# A-FINAL_SCHEMATIC.net
KiCad netlist of a schematic drawn in EAGLE
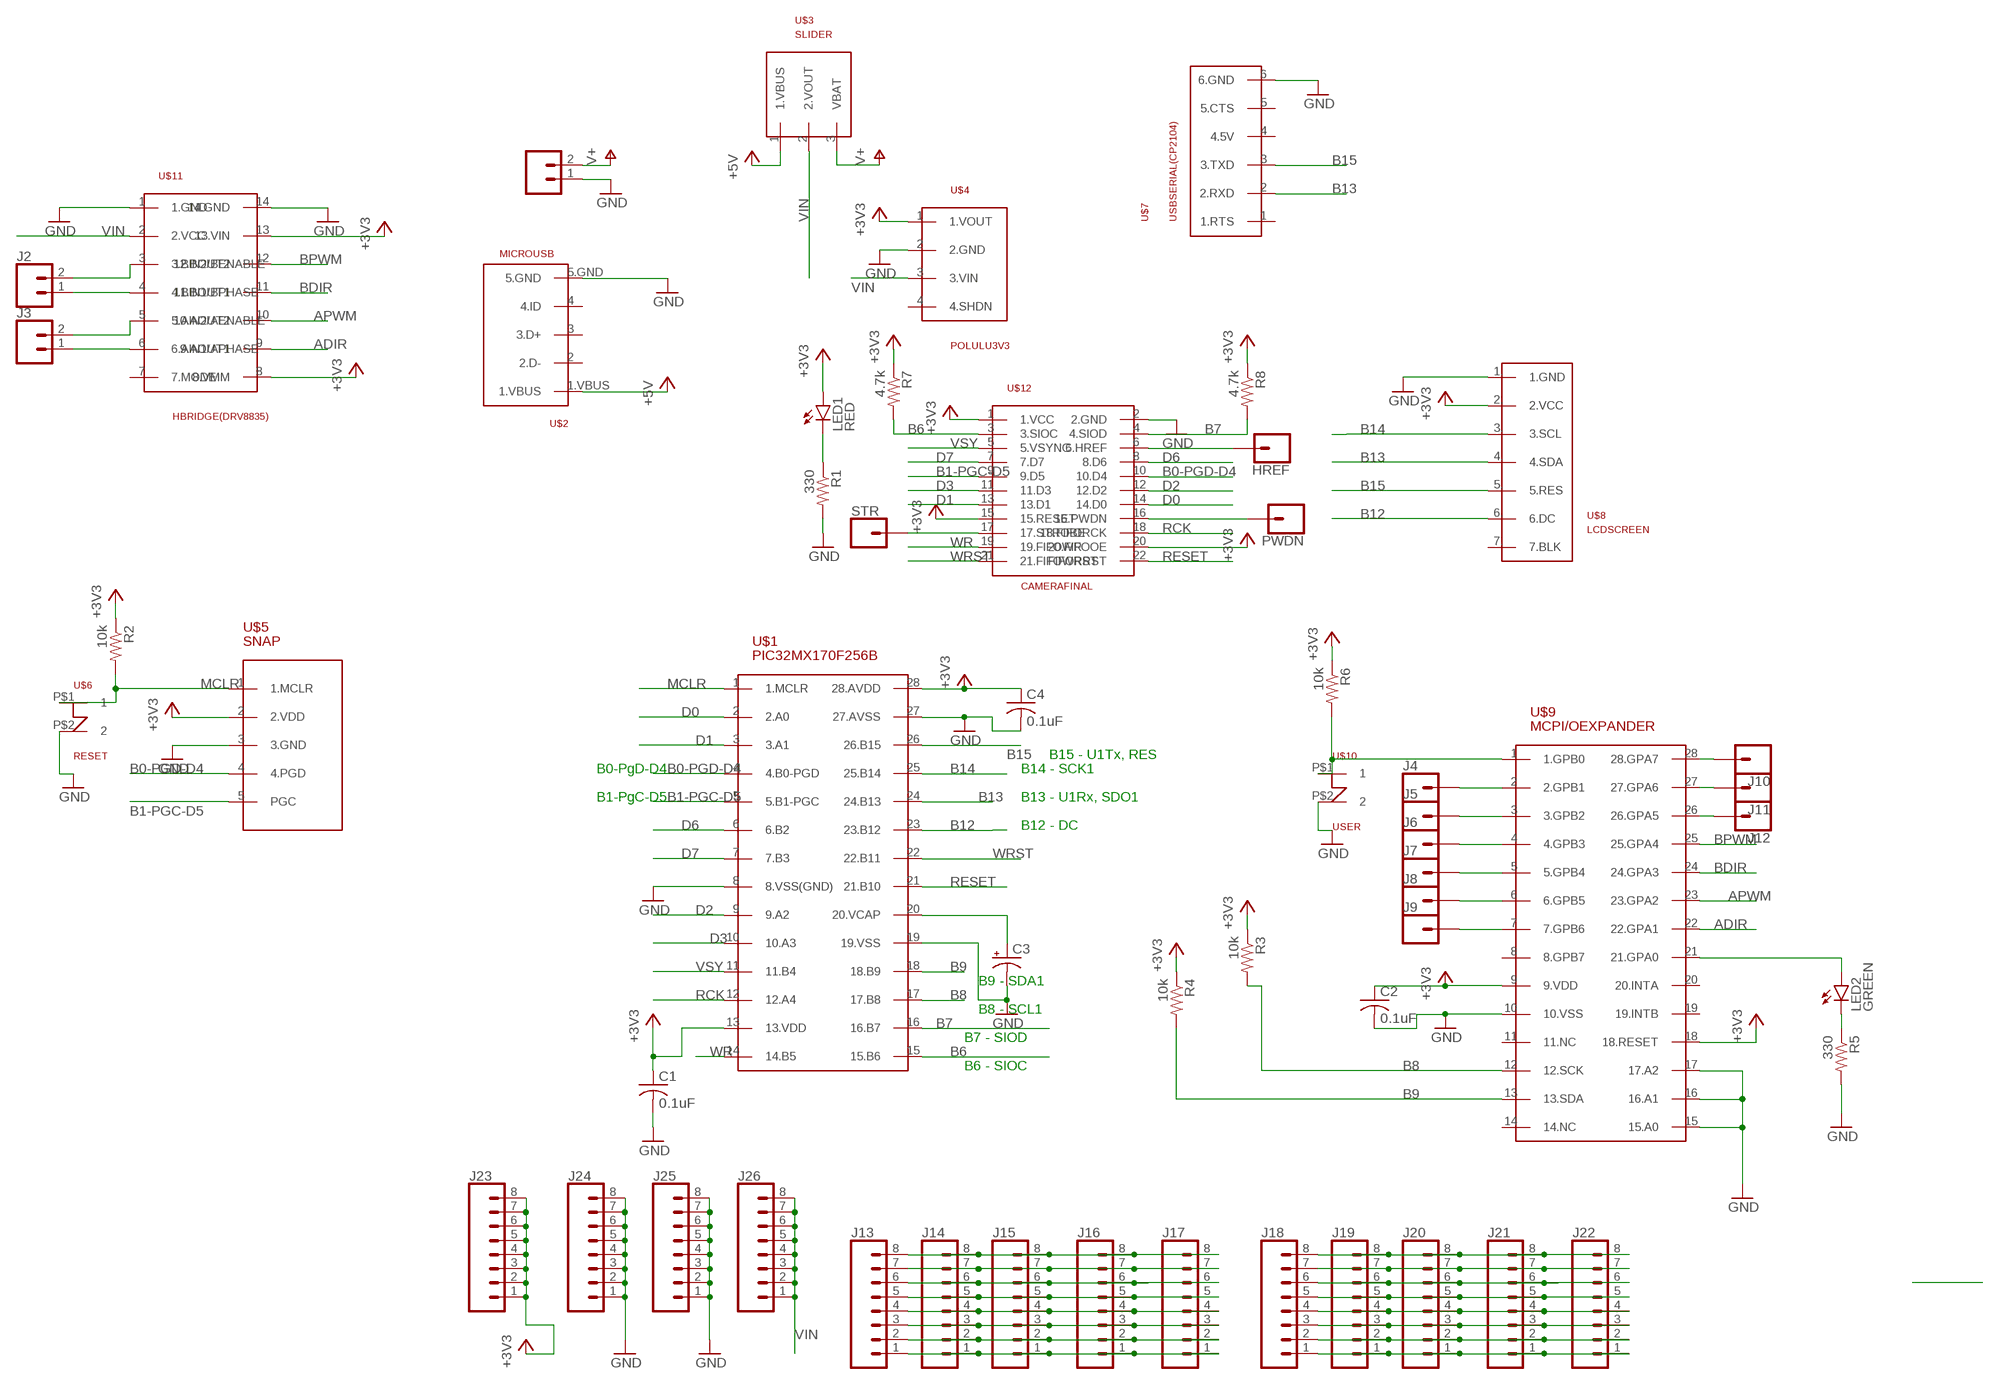
[diagram p0: schematic, sheet 1]

(export (version "E")
  (design (tool "Eeschema 10.0.6"))
  (components
    (comp (ref "C1")
      (value "0.1uF")
      (footprint "eagle-import:C025-030X050")
      (libsource (lib "eagle-import") (part "C-US025-030X050"))
    )
    (comp (ref "C2")
      (value "0.1uF")
      (footprint "eagle-import:C025-030X050")
      (libsource (lib "eagle-import") (part "C-US025-030X050"))
    )
    (comp (ref "C3")
      (value "CPOL-USB45181B")
      (footprint "eagle-import:B45181B")
      (libsource (lib "eagle-import") (part "CPOL-USB45181B"))
    )
    (comp (ref "C4")
      (value "0.1uF")
      (footprint "eagle-import:C025-030X050")
      (libsource (lib "eagle-import") (part "C-US025-030X050"))
    )
    (comp (ref "HREF")
      (value "CONN_01")
      (footprint "eagle-import:1X01")
      (libsource (lib "eagle-import") (part "CONN_01"))
    )
    (comp (ref "J1")
      (value "CONN_02-JST-2-PTH-NO_SILK")
      (footprint "eagle-import:JST-2-PTH-NS")
      (libsource (lib "eagle-import") (part "CONN_02-JST-2-PTH-NO_SILK"))
    )
    (comp (ref "J2")
      (value "CONN_02")
      (footprint "eagle-import:1X02")
      (libsource (lib "eagle-import") (part "CONN_02"))
    )
    (comp (ref "J3")
      (value "CONN_02")
      (footprint "eagle-import:1X02")
      (libsource (lib "eagle-import") (part "CONN_02"))
    )
    (comp (ref "J4")
      (value "CONN_01")
      (footprint "eagle-import:1X01")
      (libsource (lib "eagle-import") (part "CONN_01"))
    )
    (comp (ref "J5")
      (value "CONN_01")
      (footprint "eagle-import:1X01")
      (libsource (lib "eagle-import") (part "CONN_01"))
    )
    (comp (ref "J6")
      (value "CONN_01")
      (footprint "eagle-import:1X01")
      (libsource (lib "eagle-import") (part "CONN_01"))
    )
    (comp (ref "J7")
      (value "CONN_01")
      (footprint "eagle-import:1X01")
      (libsource (lib "eagle-import") (part "CONN_01"))
    )
    (comp (ref "J8")
      (value "CONN_01")
      (footprint "eagle-import:1X01")
      (libsource (lib "eagle-import") (part "CONN_01"))
    )
    (comp (ref "J9")
      (value "CONN_01")
      (footprint "eagle-import:1X01")
      (libsource (lib "eagle-import") (part "CONN_01"))
    )
    (comp (ref "J10")
      (value "CONN_01")
      (footprint "eagle-import:1X01")
      (libsource (lib "eagle-import") (part "CONN_01"))
    )
    (comp (ref "J11")
      (value "CONN_01")
      (footprint "eagle-import:1X01")
      (libsource (lib "eagle-import") (part "CONN_01"))
    )
    (comp (ref "J12")
      (value "CONN_01")
      (footprint "eagle-import:1X01")
      (libsource (lib "eagle-import") (part "CONN_01"))
    )
    (comp (ref "J13")
      (value "CONN_08\"")
      (footprint "eagle-import:1X08")
      (libsource (lib "eagle-import") (part "CONN_08{dblquote}"))
    )
    (comp (ref "J14")
      (value "CONN_08\"")
      (footprint "eagle-import:1X08")
      (libsource (lib "eagle-import") (part "CONN_08{dblquote}"))
    )
    (comp (ref "J15")
      (value "CONN_08\"")
      (footprint "eagle-import:1X08")
      (libsource (lib "eagle-import") (part "CONN_08{dblquote}"))
    )
    (comp (ref "J16")
      (value "CONN_08\"")
      (footprint "eagle-import:1X08")
      (libsource (lib "eagle-import") (part "CONN_08{dblquote}"))
    )
    (comp (ref "J17")
      (value "CONN_08\"")
      (footprint "eagle-import:1X08")
      (libsource (lib "eagle-import") (part "CONN_08{dblquote}"))
    )
    (comp (ref "J18")
      (value "CONN_08\"")
      (footprint "eagle-import:1X08")
      (libsource (lib "eagle-import") (part "CONN_08{dblquote}"))
    )
    (comp (ref "J19")
      (value "CONN_08\"")
      (footprint "eagle-import:1X08")
      (libsource (lib "eagle-import") (part "CONN_08{dblquote}"))
    )
    (comp (ref "J20")
      (value "CONN_08\"")
      (footprint "eagle-import:1X08")
      (libsource (lib "eagle-import") (part "CONN_08{dblquote}"))
    )
    (comp (ref "J21")
      (value "CONN_08\"")
      (footprint "eagle-import:1X08")
      (libsource (lib "eagle-import") (part "CONN_08{dblquote}"))
    )
    (comp (ref "J22")
      (value "CONN_08\"")
      (footprint "eagle-import:1X08")
      (libsource (lib "eagle-import") (part "CONN_08{dblquote}"))
    )
    (comp (ref "J23")
      (value "CONN_08\"")
      (footprint "eagle-import:1X08")
      (libsource (lib "eagle-import") (part "CONN_08{dblquote}"))
    )
    (comp (ref "J24")
      (value "CONN_08\"")
      (footprint "eagle-import:1X08")
      (libsource (lib "eagle-import") (part "CONN_08{dblquote}"))
    )
    (comp (ref "J25")
      (value "CONN_08\"")
      (footprint "eagle-import:1X08")
      (libsource (lib "eagle-import") (part "CONN_08{dblquote}"))
    )
    (comp (ref "J26")
      (value "CONN_08\"")
      (footprint "eagle-import:1X08")
      (libsource (lib "eagle-import") (part "CONN_08{dblquote}"))
    )
    (comp (ref "LED1")
      (value "RED")
      (footprint "eagle-import:LED3MM")
      (libsource (lib "eagle-import") (part "LED3MM"))
    )
    (comp (ref "LED2")
      (value "GREEN")
      (footprint "eagle-import:LED3MM")
      (libsource (lib "eagle-import") (part "LED3MM"))
    )
    (comp (ref "PWDN")
      (value "CONN_01")
      (footprint "eagle-import:1X01")
      (libsource (lib "eagle-import") (part "CONN_01"))
    )
    (comp (ref "R1")
      (value "330")
      (footprint "eagle-import:0207_10")
      (libsource (lib "eagle-import") (part "R-US_0207/10"))
    )
    (comp (ref "R2")
      (value "10k")
      (footprint "eagle-import:0207_10")
      (libsource (lib "eagle-import") (part "R-US_0207/10"))
    )
    (comp (ref "R3")
      (value "10k")
      (footprint "eagle-import:0207_10")
      (libsource (lib "eagle-import") (part "R-US_0207/10"))
    )
    (comp (ref "R4")
      (value "10k")
      (footprint "eagle-import:0207_10")
      (libsource (lib "eagle-import") (part "R-US_0207/10"))
    )
    (comp (ref "R5")
      (value "330")
      (footprint "eagle-import:0207_10")
      (libsource (lib "eagle-import") (part "R-US_0207/10"))
    )
    (comp (ref "R6")
      (value "10k")
      (footprint "eagle-import:0207_10")
      (libsource (lib "eagle-import") (part "R-US_0207/10"))
    )
    (comp (ref "R7")
      (value "4.7k")
      (footprint "eagle-import:0207_10")
      (libsource (lib "eagle-import") (part "R-US_0207/10"))
    )
    (comp (ref "R8")
      (value "4.7k")
      (footprint "eagle-import:0207_10")
      (libsource (lib "eagle-import") (part "R-US_0207/10"))
    )
    (comp (ref "STR")
      (value "CONN_01")
      (footprint "eagle-import:1X01")
      (libsource (lib "eagle-import") (part "CONN_01"))
    )
    (comp (ref "U$1")
      (value "PIC32MX170F256B")
      (footprint "eagle-import:DIL28-3")
      (libsource (lib "eagle-import") (part "PIC32MX170F256B"))
    )
    (comp (ref "U$2")
      (value "MICROUSB")
      (footprint "eagle-import:MICROUSB")
      (libsource (lib "eagle-import") (part "MICROUSB"))
    )
    (comp (ref "U$3")
      (value "SLIDER")
      (footprint "eagle-import:SLIDE")
      (libsource (lib "eagle-import") (part "SLIDER"))
    )
    (comp (ref "U$4")
      (value "POLULU3V3")
      (footprint "eagle-import:POLULU3V3")
      (libsource (lib "eagle-import") (part "POLULU3V3"))
    )
    (comp (ref "U$5")
      (value "SNAP")
      (footprint "eagle-import:1X05")
      (libsource (lib "eagle-import") (part "SNAP"))
    )
    (comp (ref "U$6")
      (value "RESET")
      (footprint "eagle-import:PUSH")
      (libsource (lib "eagle-import") (part "PUSH"))
    )
    (comp (ref "U$7")
      (value "USBSERIAL(CP2104)")
      (footprint "eagle-import:USBSERIAL(CP2104)")
      (libsource (lib "eagle-import") (part "USBSERIAL(CP2104)"))
    )
    (comp (ref "U$8")
      (value "LCDSCREEN")
      (footprint "eagle-import:LCDSCREEN")
      (libsource (lib "eagle-import") (part "LCDSCREEN"))
    )
    (comp (ref "U$9")
      (value "MCPI/OEXPANDER")
      (footprint "eagle-import:MCPI_OEXPANDER")
      (libsource (lib "eagle-import") (part "MCPI/OEXPANDER"))
    )
    (comp (ref "U$10")
      (value "USER")
      (footprint "eagle-import:PUSH")
      (libsource (lib "eagle-import") (part "PUSH"))
    )
    (comp (ref "U$11")
      (value "HBRIDGE(DRV8835)")
      (footprint "eagle-import:HBRIDGE(DRV8835)")
      (libsource (lib "eagle-import") (part "HBRIDGE(DRV8835)"))
    )
    (comp (ref "U$12")
      (value "CAMERAFINAL")
      (footprint "eagle-import:CAMERA_FINAL")
      (libsource (lib "eagle-import") (part "CAMERAFINAL"))
    )
  )
  (nets
    (net (code "1") (name "+3V3") (class "Default")
      (node (ref "C1") (pin "1") (pinfunction "1_1") (pintype "passive"))
      (node (ref "C2") (pin "1") (pinfunction "1_1") (pintype "passive"))
      (node (ref "C4") (pin "1") (pinfunction "1_1") (pintype "passive"))
      (node (ref "J23") (pin "1") (pinfunction "1_1") (pintype "passive"))
      (node (ref "J23") (pin "2") (pinfunction "2_2") (pintype "passive"))
      (node (ref "J23") (pin "3") (pinfunction "3_3") (pintype "passive"))
      (node (ref "J23") (pin "4") (pinfunction "4_4") (pintype "passive"))
      (node (ref "J23") (pin "5") (pinfunction "5_5") (pintype "passive"))
      (node (ref "J23") (pin "6") (pinfunction "6_6") (pintype "passive"))
      (node (ref "J23") (pin "7") (pinfunction "7_7") (pintype "passive"))
      (node (ref "J23") (pin "8") (pinfunction "8_8") (pintype "passive"))
      (node (ref "LED1") (pin "A") (pinfunction "A_A") (pintype "passive"))
      (node (ref "R2") (pin "1") (pinfunction "1_1") (pintype "passive"))
      (node (ref "R3") (pin "1") (pinfunction "1_1") (pintype "passive"))
      (node (ref "R4") (pin "1") (pinfunction "1_1") (pintype "passive"))
      (node (ref "R6") (pin "1") (pinfunction "1_1") (pintype "passive"))
      (node (ref "R7") (pin "1") (pinfunction "1_1") (pintype "passive"))
      (node (ref "R8") (pin "1") (pinfunction "1_1") (pintype "passive"))
      (node (ref "U$1") (pin "13") (pinfunction "13.VDD_13") (pintype "bidirectional"))
      (node (ref "U$1") (pin "28") (pinfunction "28.AVDD_28") (pintype "bidirectional"))
      (node (ref "U$11") (pin "13") (pinfunction "13.VIN_13") (pintype "bidirectional"))
      (node (ref "U$11") (pin "8") (pinfunction "8.VMM_8") (pintype "bidirectional"))
      (node (ref "U$12") (pin "1") (pinfunction "1.VCC_1") (pintype "bidirectional"))
      (node (ref "U$12") (pin "15") (pinfunction "15.RESET_15") (pintype "bidirectional"))
      (node (ref "U$12") (pin "20") (pinfunction "20.FIFOOE_20") (pintype "bidirectional"))
      (node (ref "U$4") (pin "1") (pinfunction "1.VOUT_1") (pintype "bidirectional"))
      (node (ref "U$5") (pin "2") (pinfunction "2.VDD_2") (pintype "bidirectional"))
      (node (ref "U$8") (pin "2.") (pinfunction "2.VCC_2.") (pintype "bidirectional"))
      (node (ref "U$9") (pin "18") (pinfunction "18.RESET_18") (pintype "bidirectional"))
      (node (ref "U$9") (pin "9") (pinfunction "9.VDD_9") (pintype "bidirectional"))
    )
    (net (code "2") (name "+5V") (class "Default")
      (node (ref "U$2") (pin "1.VBUS") (pinfunction "1.VBUS_1.VBUS") (pintype "bidirectional"))
      (node (ref "U$3") (pin "1") (pinfunction "1.VBUS_1") (pintype "bidirectional"))
    )
    (net (code "3") (name "/ADIR") (class "Default")
      (node (ref "U$11") (pin "9") (pinfunction "9.AOUT1_9") (pintype "bidirectional"))
      (node (ref "U$9") (pin "22") (pinfunction "22.GPA1_22") (pintype "bidirectional"))
    )
    (net (code "4") (name "/APWM") (class "Default")
      (node (ref "U$11") (pin "10") (pinfunction "10.AOUT2_10") (pintype "bidirectional"))
      (node (ref "U$9") (pin "23") (pinfunction "23.GPA2_23") (pintype "bidirectional"))
    )
    (net (code "5") (name "/B0-PGD-D4") (class "Default")
      (node (ref "U$1") (pin "4") (pinfunction "4.B0-PGD_4") (pintype "bidirectional"))
      (node (ref "U$12") (pin "10") (pinfunction "10.D4_10") (pintype "bidirectional"))
      (node (ref "U$5") (pin "4") (pinfunction "4.PGD_4") (pintype "bidirectional"))
    )
    (net (code "6") (name "/B1-PGC-D5") (class "Default")
      (node (ref "U$1") (pin "5") (pinfunction "5.B1-PGC_5") (pintype "bidirectional"))
      (node (ref "U$12") (pin "9") (pinfunction "9.D5_9") (pintype "bidirectional"))
      (node (ref "U$5") (pin "5") (pinfunction "PGC_5") (pintype "bidirectional"))
    )
    (net (code "7") (name "/B6") (class "Default")
      (node (ref "R7") (pin "2") (pinfunction "2_2") (pintype "passive"))
      (node (ref "U$1") (pin "15") (pinfunction "15.B6_15") (pintype "bidirectional"))
      (node (ref "U$12") (pin "3") (pinfunction "3.SIOC_3") (pintype "bidirectional"))
    )
    (net (code "8") (name "/B7") (class "Default")
      (node (ref "R8") (pin "2") (pinfunction "2_2") (pintype "passive"))
      (node (ref "U$1") (pin "16") (pinfunction "16.B7_16") (pintype "bidirectional"))
      (node (ref "U$12") (pin "4") (pinfunction "4.SIOD_4") (pintype "bidirectional"))
    )
    (net (code "9") (name "/B8") (class "Default")
      (node (ref "R3") (pin "2") (pinfunction "2_2") (pintype "passive"))
      (node (ref "U$1") (pin "17") (pinfunction "17.B8_17") (pintype "bidirectional"))
      (node (ref "U$9") (pin "12") (pinfunction "12.SCK_12") (pintype "bidirectional"))
    )
    (net (code "10") (name "/B9") (class "Default")
      (node (ref "R4") (pin "2") (pinfunction "2_2") (pintype "passive"))
      (node (ref "U$1") (pin "18") (pinfunction "18.B9_18") (pintype "bidirectional"))
      (node (ref "U$9") (pin "13") (pinfunction "13.SDA_13") (pintype "bidirectional"))
    )
    (net (code "11") (name "/B12") (class "Default")
      (node (ref "U$1") (pin "23") (pinfunction "23.B12_23") (pintype "bidirectional"))
      (node (ref "U$8") (pin "6.") (pinfunction "6.DC_6.") (pintype "bidirectional"))
    )
    (net (code "12") (name "/B13") (class "Default")
      (node (ref "U$1") (pin "24") (pinfunction "24.B13_24") (pintype "bidirectional"))
      (node (ref "U$7") (pin "2") (pinfunction "2.RXD_2") (pintype "bidirectional"))
      (node (ref "U$8") (pin "4.") (pinfunction "4.SDA_4.") (pintype "bidirectional"))
    )
    (net (code "13") (name "/B14") (class "Default")
      (node (ref "U$1") (pin "25") (pinfunction "25.B14_25") (pintype "bidirectional"))
      (node (ref "U$8") (pin "3.") (pinfunction "3.SCL_3.") (pintype "bidirectional"))
    )
    (net (code "14") (name "/B15") (class "Default")
      (node (ref "U$1") (pin "26") (pinfunction "26.B15_26") (pintype "bidirectional"))
      (node (ref "U$7") (pin "3") (pinfunction "3.TXD_3") (pintype "bidirectional"))
      (node (ref "U$8") (pin "5.") (pinfunction "5.RES_5.") (pintype "bidirectional"))
    )
    (net (code "15") (name "/BDIR") (class "Default")
      (node (ref "U$11") (pin "11") (pinfunction "11.BOUT1_11") (pintype "bidirectional"))
      (node (ref "U$9") (pin "24") (pinfunction "24.GPA3_24") (pintype "bidirectional"))
    )
    (net (code "16") (name "/BPWM") (class "Default")
      (node (ref "U$11") (pin "12") (pinfunction "12.BOUT2_12") (pintype "bidirectional"))
      (node (ref "U$9") (pin "25") (pinfunction "25.GPA4_25") (pintype "bidirectional"))
    )
    (net (code "17") (name "/D0") (class "Default")
      (node (ref "U$1") (pin "2") (pinfunction "2.A0_2") (pintype "bidirectional"))
      (node (ref "U$12") (pin "14") (pinfunction "14.D0_14") (pintype "bidirectional"))
    )
    (net (code "18") (name "/D1") (class "Default")
      (node (ref "U$1") (pin "3") (pinfunction "3.A1_3") (pintype "bidirectional"))
      (node (ref "U$12") (pin "13") (pinfunction "13.D1_13") (pintype "bidirectional"))
    )
    (net (code "19") (name "/D2") (class "Default")
      (node (ref "U$1") (pin "9") (pinfunction "9.A2_9") (pintype "bidirectional"))
      (node (ref "U$12") (pin "12") (pinfunction "12.D2_12") (pintype "bidirectional"))
    )
    (net (code "20") (name "/D3") (class "Default")
      (node (ref "U$1") (pin "10") (pinfunction "10.A3_10") (pintype "bidirectional"))
      (node (ref "U$12") (pin "11") (pinfunction "11.D3_11") (pintype "bidirectional"))
    )
    (net (code "21") (name "/D6") (class "Default")
      (node (ref "U$1") (pin "6") (pinfunction "6.B2_6") (pintype "bidirectional"))
      (node (ref "U$12") (pin "8") (pinfunction "8.D6_8") (pintype "bidirectional"))
    )
    (net (code "22") (name "/D7") (class "Default")
      (node (ref "U$1") (pin "7") (pinfunction "7.B3_7") (pintype "bidirectional"))
      (node (ref "U$12") (pin "7") (pinfunction "7.D7_7") (pintype "bidirectional"))
    )
    (net (code "23") (name "/MCLR") (class "Default")
      (node (ref "R2") (pin "2") (pinfunction "2_2") (pintype "passive"))
      (node (ref "U$1") (pin "1") (pinfunction "1.MCLR_1") (pintype "bidirectional"))
      (node (ref "U$5") (pin "1") (pinfunction "1.MCLR_1") (pintype "bidirectional"))
      (node (ref "U$6") (pin "P$1") (pinfunction "1_P$1") (pintype "bidirectional"))
    )
    (net (code "24") (name "/RCK") (class "Default")
      (node (ref "U$1") (pin "12") (pinfunction "12.A4_12") (pintype "bidirectional"))
      (node (ref "U$12") (pin "18") (pinfunction "18.FIFORCK_18") (pintype "bidirectional"))
    )
    (net (code "25") (name "/RESET") (class "Default")
      (node (ref "U$1") (pin "21") (pinfunction "21.B10_21") (pintype "bidirectional"))
      (node (ref "U$12") (pin "22") (pinfunction "FIFORRST_22") (pintype "bidirectional"))
    )
    (net (code "26") (name "/VIN") (class "Default")
      (node (ref "J26") (pin "1") (pinfunction "1_1") (pintype "passive"))
      (node (ref "J26") (pin "2") (pinfunction "2_2") (pintype "passive"))
      (node (ref "J26") (pin "3") (pinfunction "3_3") (pintype "passive"))
      (node (ref "J26") (pin "4") (pinfunction "4_4") (pintype "passive"))
      (node (ref "J26") (pin "5") (pinfunction "5_5") (pintype "passive"))
      (node (ref "J26") (pin "6") (pinfunction "6_6") (pintype "passive"))
      (node (ref "J26") (pin "7") (pinfunction "7_7") (pintype "passive"))
      (node (ref "J26") (pin "8") (pinfunction "8_8") (pintype "passive"))
      (node (ref "U$11") (pin "2") (pinfunction "2.VCC_2") (pintype "bidirectional"))
      (node (ref "U$3") (pin "2") (pinfunction "2.VOUT_2") (pintype "bidirectional"))
      (node (ref "U$4") (pin "3") (pinfunction "3.VIN_3") (pintype "bidirectional"))
    )
    (net (code "27") (name "/VSY") (class "Default")
      (node (ref "U$1") (pin "11") (pinfunction "11.B4_11") (pintype "bidirectional"))
      (node (ref "U$12") (pin "5") (pinfunction "5.VSYNC_5") (pintype "bidirectional"))
    )
    (net (code "28") (name "/WR") (class "Default")
      (node (ref "U$1") (pin "14") (pinfunction "14.B5_14") (pintype "bidirectional"))
      (node (ref "U$12") (pin "19") (pinfunction "19.FIFOWR_19") (pintype "bidirectional"))
    )
    (net (code "29") (name "/WRST") (class "Default")
      (node (ref "U$1") (pin "22") (pinfunction "22.B11_22") (pintype "bidirectional"))
      (node (ref "U$12") (pin "21") (pinfunction "21.FIFOWRST_21") (pintype "bidirectional"))
    )
    (net (code "30") (name "GND") (class "Default")
      (node (ref "C1") (pin "2") (pinfunction "2_2") (pintype "passive"))
      (node (ref "C2") (pin "2") (pinfunction "2_2") (pintype "passive"))
      (node (ref "C3") (pin "-") (pinfunction "-_-") (pintype "passive"))
      (node (ref "C4") (pin "2") (pinfunction "2_2") (pintype "passive"))
      (node (ref "J1") (pin "1") (pinfunction "1_1") (pintype "passive"))
      (node (ref "J24") (pin "1") (pinfunction "1_1") (pintype "passive"))
      (node (ref "J24") (pin "2") (pinfunction "2_2") (pintype "passive"))
      (node (ref "J24") (pin "3") (pinfunction "3_3") (pintype "passive"))
      (node (ref "J24") (pin "4") (pinfunction "4_4") (pintype "passive"))
      (node (ref "J24") (pin "5") (pinfunction "5_5") (pintype "passive"))
      (node (ref "J24") (pin "6") (pinfunction "6_6") (pintype "passive"))
      (node (ref "J24") (pin "7") (pinfunction "7_7") (pintype "passive"))
      (node (ref "J24") (pin "8") (pinfunction "8_8") (pintype "passive"))
      (node (ref "J25") (pin "1") (pinfunction "1_1") (pintype "passive"))
      (node (ref "J25") (pin "2") (pinfunction "2_2") (pintype "passive"))
      (node (ref "J25") (pin "3") (pinfunction "3_3") (pintype "passive"))
      (node (ref "J25") (pin "4") (pinfunction "4_4") (pintype "passive"))
      (node (ref "J25") (pin "5") (pinfunction "5_5") (pintype "passive"))
      (node (ref "J25") (pin "6") (pinfunction "6_6") (pintype "passive"))
      (node (ref "J25") (pin "7") (pinfunction "7_7") (pintype "passive"))
      (node (ref "J25") (pin "8") (pinfunction "8_8") (pintype "passive"))
      (node (ref "R1") (pin "2") (pinfunction "2_2") (pintype "passive"))
      (node (ref "R5") (pin "2") (pinfunction "2_2") (pintype "passive"))
      (node (ref "U$1") (pin "19") (pinfunction "19.VSS_19") (pintype "bidirectional"))
      (node (ref "U$1") (pin "27") (pinfunction "27.AVSS_27") (pintype "bidirectional"))
      (node (ref "U$1") (pin "8") (pinfunction "8.VSS(GND)_8") (pintype "bidirectional"))
      (node (ref "U$10") (pin "P$2") (pinfunction "2_P$2") (pintype "bidirectional"))
      (node (ref "U$11") (pin "1") (pinfunction "1.GND_1") (pintype "bidirectional"))
      (node (ref "U$11") (pin "14") (pinfunction "14.GND_14") (pintype "bidirectional"))
      (node (ref "U$12") (pin "2") (pinfunction "2.GND_2") (pintype "bidirectional"))
      (node (ref "U$2") (pin "5.GND") (pinfunction "5.GND_5.GND") (pintype "bidirectional"))
      (node (ref "U$4") (pin "2") (pinfunction "2.GND_2") (pintype "bidirectional"))
      (node (ref "U$5") (pin "3") (pinfunction "3.GND_3") (pintype "bidirectional"))
      (node (ref "U$6") (pin "P$2") (pinfunction "2_P$2") (pintype "bidirectional"))
      (node (ref "U$7") (pin "6") (pinfunction "6.GND_6") (pintype "bidirectional"))
      (node (ref "U$8") (pin "1.") (pinfunction "1.GND_1.") (pintype "bidirectional"))
      (node (ref "U$9") (pin "10") (pinfunction "10.VSS_10") (pintype "bidirectional"))
      (node (ref "U$9") (pin "15") (pinfunction "15.A0_15") (pintype "bidirectional"))
      (node (ref "U$9") (pin "16") (pinfunction "16.A1_16") (pintype "bidirectional"))
      (node (ref "U$9") (pin "17") (pinfunction "17.A2_17") (pintype "bidirectional"))
    )
    (net (code "31") (name "Net-(J13-Pad1)") (class "Default")
      (node (ref "J13") (pin "1") (pinfunction "1_1") (pintype "passive"))
      (node (ref "J14") (pin "1") (pinfunction "1_1") (pintype "passive"))
      (node (ref "J15") (pin "1") (pinfunction "1_1") (pintype "passive"))
      (node (ref "J16") (pin "1") (pinfunction "1_1") (pintype "passive"))
      (node (ref "J17") (pin "1") (pinfunction "1_1") (pintype "passive"))
    )
    (net (code "32") (name "Net-(J13-Pad2)") (class "Default")
      (node (ref "J13") (pin "2") (pinfunction "2_2") (pintype "passive"))
      (node (ref "J14") (pin "2") (pinfunction "2_2") (pintype "passive"))
      (node (ref "J15") (pin "2") (pinfunction "2_2") (pintype "passive"))
      (node (ref "J16") (pin "2") (pinfunction "2_2") (pintype "passive"))
      (node (ref "J17") (pin "2") (pinfunction "2_2") (pintype "passive"))
    )
    (net (code "33") (name "Net-(J13-Pad3)") (class "Default")
      (node (ref "J13") (pin "3") (pinfunction "3_3") (pintype "passive"))
      (node (ref "J14") (pin "3") (pinfunction "3_3") (pintype "passive"))
      (node (ref "J15") (pin "3") (pinfunction "3_3") (pintype "passive"))
      (node (ref "J16") (pin "3") (pinfunction "3_3") (pintype "passive"))
      (node (ref "J17") (pin "3") (pinfunction "3_3") (pintype "passive"))
    )
    (net (code "34") (name "Net-(J13-Pad4)") (class "Default")
      (node (ref "J13") (pin "4") (pinfunction "4_4") (pintype "passive"))
      (node (ref "J14") (pin "4") (pinfunction "4_4") (pintype "passive"))
      (node (ref "J15") (pin "4") (pinfunction "4_4") (pintype "passive"))
      (node (ref "J16") (pin "4") (pinfunction "4_4") (pintype "passive"))
      (node (ref "J17") (pin "4") (pinfunction "4_4") (pintype "passive"))
    )
    (net (code "35") (name "Net-(J13-Pad5)") (class "Default")
      (node (ref "J13") (pin "5") (pinfunction "5_5") (pintype "passive"))
      (node (ref "J14") (pin "5") (pinfunction "5_5") (pintype "passive"))
      (node (ref "J15") (pin "5") (pinfunction "5_5") (pintype "passive"))
      (node (ref "J16") (pin "5") (pinfunction "5_5") (pintype "passive"))
      (node (ref "J17") (pin "5") (pinfunction "5_5") (pintype "passive"))
    )
    (net (code "36") (name "Net-(J13-Pad6)") (class "Default")
      (node (ref "J13") (pin "6") (pinfunction "6_6") (pintype "passive"))
      (node (ref "J14") (pin "6") (pinfunction "6_6") (pintype "passive"))
      (node (ref "J15") (pin "6") (pinfunction "6_6") (pintype "passive"))
      (node (ref "J16") (pin "6") (pinfunction "6_6") (pintype "passive"))
      (node (ref "J17") (pin "6") (pinfunction "6_6") (pintype "passive"))
    )
    (net (code "37") (name "Net-(J13-Pad7)") (class "Default")
      (node (ref "J13") (pin "7") (pinfunction "7_7") (pintype "passive"))
      (node (ref "J14") (pin "7") (pinfunction "7_7") (pintype "passive"))
      (node (ref "J15") (pin "7") (pinfunction "7_7") (pintype "passive"))
      (node (ref "J16") (pin "7") (pinfunction "7_7") (pintype "passive"))
      (node (ref "J17") (pin "7") (pinfunction "7_7") (pintype "passive"))
    )
    (net (code "38") (name "Net-(J13-Pad8)") (class "Default")
      (node (ref "J13") (pin "8") (pinfunction "8_8") (pintype "passive"))
      (node (ref "J14") (pin "8") (pinfunction "8_8") (pintype "passive"))
      (node (ref "J15") (pin "8") (pinfunction "8_8") (pintype "passive"))
      (node (ref "J16") (pin "8") (pinfunction "8_8") (pintype "passive"))
      (node (ref "J17") (pin "8") (pinfunction "8_8") (pintype "passive"))
    )
    (net (code "39") (name "Net-(J18-Pad1)") (class "Default")
      (node (ref "J18") (pin "1") (pinfunction "1_1") (pintype "passive"))
      (node (ref "J19") (pin "1") (pinfunction "1_1") (pintype "passive"))
      (node (ref "J20") (pin "1") (pinfunction "1_1") (pintype "passive"))
      (node (ref "J21") (pin "1") (pinfunction "1_1") (pintype "passive"))
      (node (ref "J22") (pin "1") (pinfunction "1_1") (pintype "passive"))
    )
    (net (code "40") (name "Net-(J18-Pad2)") (class "Default")
      (node (ref "J18") (pin "2") (pinfunction "2_2") (pintype "passive"))
      (node (ref "J19") (pin "2") (pinfunction "2_2") (pintype "passive"))
      (node (ref "J20") (pin "2") (pinfunction "2_2") (pintype "passive"))
      (node (ref "J21") (pin "2") (pinfunction "2_2") (pintype "passive"))
      (node (ref "J22") (pin "2") (pinfunction "2_2") (pintype "passive"))
    )
    (net (code "41") (name "Net-(J18-Pad3)") (class "Default")
      (node (ref "J18") (pin "3") (pinfunction "3_3") (pintype "passive"))
      (node (ref "J19") (pin "3") (pinfunction "3_3") (pintype "passive"))
      (node (ref "J20") (pin "3") (pinfunction "3_3") (pintype "passive"))
      (node (ref "J21") (pin "3") (pinfunction "3_3") (pintype "passive"))
      (node (ref "J22") (pin "3") (pinfunction "3_3") (pintype "passive"))
    )
    (net (code "42") (name "Net-(J18-Pad4)") (class "Default")
      (node (ref "J18") (pin "4") (pinfunction "4_4") (pintype "passive"))
      (node (ref "J19") (pin "4") (pinfunction "4_4") (pintype "passive"))
      (node (ref "J20") (pin "4") (pinfunction "4_4") (pintype "passive"))
      (node (ref "J21") (pin "4") (pinfunction "4_4") (pintype "passive"))
      (node (ref "J22") (pin "4") (pinfunction "4_4") (pintype "passive"))
    )
    (net (code "43") (name "Net-(J18-Pad5)") (class "Default")
      (node (ref "J18") (pin "5") (pinfunction "5_5") (pintype "passive"))
      (node (ref "J19") (pin "5") (pinfunction "5_5") (pintype "passive"))
      (node (ref "J20") (pin "5") (pinfunction "5_5") (pintype "passive"))
      (node (ref "J21") (pin "5") (pinfunction "5_5") (pintype "passive"))
      (node (ref "J22") (pin "5") (pinfunction "5_5") (pintype "passive"))
    )
    (net (code "44") (name "Net-(J18-Pad6)") (class "Default")
      (node (ref "J18") (pin "6") (pinfunction "6_6") (pintype "passive"))
      (node (ref "J19") (pin "6") (pinfunction "6_6") (pintype "passive"))
      (node (ref "J20") (pin "6") (pinfunction "6_6") (pintype "passive"))
      (node (ref "J21") (pin "6") (pinfunction "6_6") (pintype "passive"))
      (node (ref "J22") (pin "6") (pinfunction "6_6") (pintype "passive"))
    )
    (net (code "45") (name "Net-(J18-Pad7)") (class "Default")
      (node (ref "J18") (pin "7") (pinfunction "7_7") (pintype "passive"))
      (node (ref "J19") (pin "7") (pinfunction "7_7") (pintype "passive"))
      (node (ref "J20") (pin "7") (pinfunction "7_7") (pintype "passive"))
      (node (ref "J21") (pin "7") (pinfunction "7_7") (pintype "passive"))
      (node (ref "J22") (pin "7") (pinfunction "7_7") (pintype "passive"))
    )
    (net (code "46") (name "Net-(J18-Pad8)") (class "Default")
      (node (ref "J18") (pin "8") (pinfunction "8_8") (pintype "passive"))
      (node (ref "J19") (pin "8") (pinfunction "8_8") (pintype "passive"))
      (node (ref "J20") (pin "8") (pinfunction "8_8") (pintype "passive"))
      (node (ref "J21") (pin "8") (pinfunction "8_8") (pintype "passive"))
      (node (ref "J22") (pin "8") (pinfunction "8_8") (pintype "passive"))
    )
    (net (code "47") (name "Net-(LED1-C)") (class "Default")
      (node (ref "LED1") (pin "K") (pinfunction "C_K") (pintype "passive"))
      (node (ref "R1") (pin "1") (pinfunction "1_1") (pintype "passive"))
    )
    (net (code "48") (name "Net-(LED2-C)") (class "Default")
      (node (ref "LED2") (pin "K") (pinfunction "C_K") (pintype "passive"))
      (node (ref "R5") (pin "1") (pinfunction "1_1") (pintype "passive"))
    )
    (net (code "49") (name "Net-(U$1-20.VCAP)") (class "Default")
      (node (ref "C3") (pin "+") (pinfunction "+_+") (pintype "passive"))
      (node (ref "U$1") (pin "20") (pinfunction "20.VCAP_20") (pintype "bidirectional"))
    )
    (net (code "50") (name "Net-(U$9-2.GPB1)") (class "Default")
      (node (ref "J4") (pin "1") (pinfunction "1_1") (pintype "passive"))
      (node (ref "U$9") (pin "2") (pinfunction "2.GPB1_2") (pintype "bidirectional"))
    )
    (net (code "51") (name "Net-(U$9-3.GPB2)") (class "Default")
      (node (ref "J5") (pin "1") (pinfunction "1_1") (pintype "passive"))
      (node (ref "U$9") (pin "3") (pinfunction "3.GPB2_3") (pintype "bidirectional"))
    )
    (net (code "52") (name "Net-(U$9-4.GPB3)") (class "Default")
      (node (ref "J6") (pin "1") (pinfunction "1_1") (pintype "passive"))
      (node (ref "U$9") (pin "4") (pinfunction "4.GPB3_4") (pintype "bidirectional"))
    )
    (net (code "53") (name "Net-(U$9-5.GPB4)") (class "Default")
      (node (ref "J7") (pin "1") (pinfunction "1_1") (pintype "passive"))
      (node (ref "U$9") (pin "5") (pinfunction "5.GPB4_5") (pintype "bidirectional"))
    )
    (net (code "54") (name "Net-(U$9-6.GPB5)") (class "Default")
      (node (ref "J8") (pin "1") (pinfunction "1_1") (pintype "passive"))
      (node (ref "U$9") (pin "6") (pinfunction "6.GPB5_6") (pintype "bidirectional"))
    )
    (net (code "55") (name "Net-(U$9-7.GPB6)") (class "Default")
      (node (ref "J9") (pin "1") (pinfunction "1_1") (pintype "passive"))
      (node (ref "U$9") (pin "7") (pinfunction "7.GPB6_7") (pintype "bidirectional"))
    )
    (net (code "56") (name "Net-(U$9-21.GPA0)") (class "Default")
      (node (ref "LED2") (pin "A") (pinfunction "A_A") (pintype "passive"))
      (node (ref "U$9") (pin "21") (pinfunction "21.GPA0_21") (pintype "bidirectional"))
    )
    (net (code "57") (name "Net-(U$9-26.GPA5)") (class "Default")
      (node (ref "J12") (pin "1") (pinfunction "1_1") (pintype "passive"))
      (node (ref "U$9") (pin "26") (pinfunction "26.GPA5_26") (pintype "bidirectional"))
    )
    (net (code "58") (name "Net-(U$9-27.GPA6)") (class "Default")
      (node (ref "J11") (pin "1") (pinfunction "1_1") (pintype "passive"))
      (node (ref "U$9") (pin "27") (pinfunction "27.GPA6_27") (pintype "bidirectional"))
    )
    (net (code "59") (name "Net-(U$9-28.GPA7)") (class "Default")
      (node (ref "J10") (pin "1") (pinfunction "1_1") (pintype "passive"))
      (node (ref "U$9") (pin "28") (pinfunction "28.GPA7_28") (pintype "bidirectional"))
    )
    (net (code "60") (name "Net-(U$10-1)") (class "Default")
      (node (ref "R6") (pin "2") (pinfunction "2_2") (pintype "passive"))
      (node (ref "U$10") (pin "P$1") (pinfunction "1_P$1") (pintype "bidirectional"))
      (node (ref "U$9") (pin "1") (pinfunction "1.GPB0_1") (pintype "bidirectional"))
    )
    (net (code "61") (name "Net-(U$11-3.BIN2{slash}BENABLE)") (class "Default")
      (node (ref "J2") (pin "2") (pinfunction "2_2") (pintype "passive"))
      (node (ref "U$11") (pin "3") (pinfunction "3.BIN2/BENABLE_3") (pintype "bidirectional"))
    )
    (net (code "62") (name "Net-(U$11-4.BIN1{slash}BPHASE)") (class "Default")
      (node (ref "J2") (pin "1") (pinfunction "1_1") (pintype "passive"))
      (node (ref "U$11") (pin "4") (pinfunction "4.BIN1/BPHASE_4") (pintype "bidirectional"))
    )
    (net (code "63") (name "Net-(U$11-5.AIN2{slash}AENABLE)") (class "Default")
      (node (ref "J3") (pin "2") (pinfunction "2_2") (pintype "passive"))
      (node (ref "U$11") (pin "5") (pinfunction "5.AIN2/AENABLE_5") (pintype "bidirectional"))
    )
    (net (code "64") (name "Net-(U$11-6.AIN1{slash}APHASE)") (class "Default")
      (node (ref "J3") (pin "1") (pinfunction "1_1") (pintype "passive"))
      (node (ref "U$11") (pin "6") (pinfunction "6.AIN1/APHASE_6") (pintype "bidirectional"))
    )
    (net (code "65") (name "Net-(U$12-6.HREF)") (class "Default")
      (node (ref "HREF") (pin "1") (pinfunction "1_1") (pintype "passive"))
      (node (ref "U$12") (pin "6") (pinfunction "6.HREF_6") (pintype "bidirectional"))
    )
    (net (code "66") (name "Net-(U$12-16.PWDN)") (class "Default")
      (node (ref "PWDN") (pin "1") (pinfunction "1_1") (pintype "passive"))
      (node (ref "U$12") (pin "16") (pinfunction "16.PWDN_16") (pintype "bidirectional"))
    )
    (net (code "67") (name "Net-(U$12-17.STROBE)") (class "Default")
      (node (ref "STR") (pin "1") (pinfunction "1_1") (pintype "passive"))
      (node (ref "U$12") (pin "17") (pinfunction "17.STROBE_17") (pintype "bidirectional"))
    )
    (net (code "68") (name "V+") (class "Default")
      (node (ref "J1") (pin "2") (pinfunction "2_2") (pintype "passive"))
      (node (ref "U$3") (pin "3") (pinfunction "VBAT_3") (pintype "bidirectional"))
    )
    (net (code "69") (name "unconnected-(U$2-2.D--Pad2)") (class "Default")
      (node (ref "U$2") (pin "2") (pinfunction "2.D-_2") (pintype "bidirectional"))
    )
    (net (code "70") (name "unconnected-(U$2-3.D+-Pad3)") (class "Default")
      (node (ref "U$2") (pin "3") (pinfunction "3.D+_3") (pintype "bidirectional"))
    )
    (net (code "71") (name "unconnected-(U$2-4.ID-Pad4)") (class "Default")
      (node (ref "U$2") (pin "4") (pinfunction "4.ID_4") (pintype "bidirectional"))
    )
    (net (code "72") (name "unconnected-(U$4-4.SHDN-Pad4)") (class "Default")
      (node (ref "U$4") (pin "4") (pinfunction "4.SHDN_4") (pintype "bidirectional"))
    )
    (net (code "73") (name "unconnected-(U$7-1.RTS-Pad1)") (class "Default")
      (node (ref "U$7") (pin "1") (pinfunction "1.RTS_1") (pintype "bidirectional"))
    )
    (net (code "74") (name "unconnected-(U$7-4.5V-Pad4)") (class "Default")
      (node (ref "U$7") (pin "4") (pinfunction "4.5V_4") (pintype "bidirectional"))
    )
    (net (code "75") (name "unconnected-(U$7-5.CTS-Pad5)") (class "Default")
      (node (ref "U$7") (pin "5") (pinfunction "5.CTS_5") (pintype "bidirectional"))
    )
    (net (code "76") (name "unconnected-(U$8-7.BLK-Pad7.)") (class "Default")
      (node (ref "U$8") (pin "7.") (pinfunction "7.BLK_7.") (pintype "bidirectional"))
    )
    (net (code "77") (name "unconnected-(U$9-8.GPB7-Pad8)") (class "Default")
      (node (ref "U$9") (pin "8") (pinfunction "8.GPB7_8") (pintype "bidirectional"))
    )
    (net (code "78") (name "unconnected-(U$9-11.NC-Pad11)") (class "Default")
      (node (ref "U$9") (pin "11") (pinfunction "11.NC_11") (pintype "bidirectional"))
    )
    (net (code "79") (name "unconnected-(U$9-14.NC-Pad14)") (class "Default")
      (node (ref "U$9") (pin "14") (pinfunction "14.NC_14") (pintype "bidirectional"))
    )
    (net (code "80") (name "unconnected-(U$9-19.INTB-Pad19)") (class "Default")
      (node (ref "U$9") (pin "19") (pinfunction "19.INTB_19") (pintype "bidirectional"))
    )
    (net (code "81") (name "unconnected-(U$9-20.INTA-Pad20)") (class "Default")
      (node (ref "U$9") (pin "20") (pinfunction "20.INTA_20") (pintype "bidirectional"))
    )
    (net (code "82") (name "unconnected-(U$11-7.MODE-Pad7)") (class "Default")
      (node (ref "U$11") (pin "7") (pinfunction "7.MODE_7") (pintype "bidirectional"))
    )
  )
)
